# Maiskolben_THT.net
KiCad netlist of a schematic drawn in EAGLE
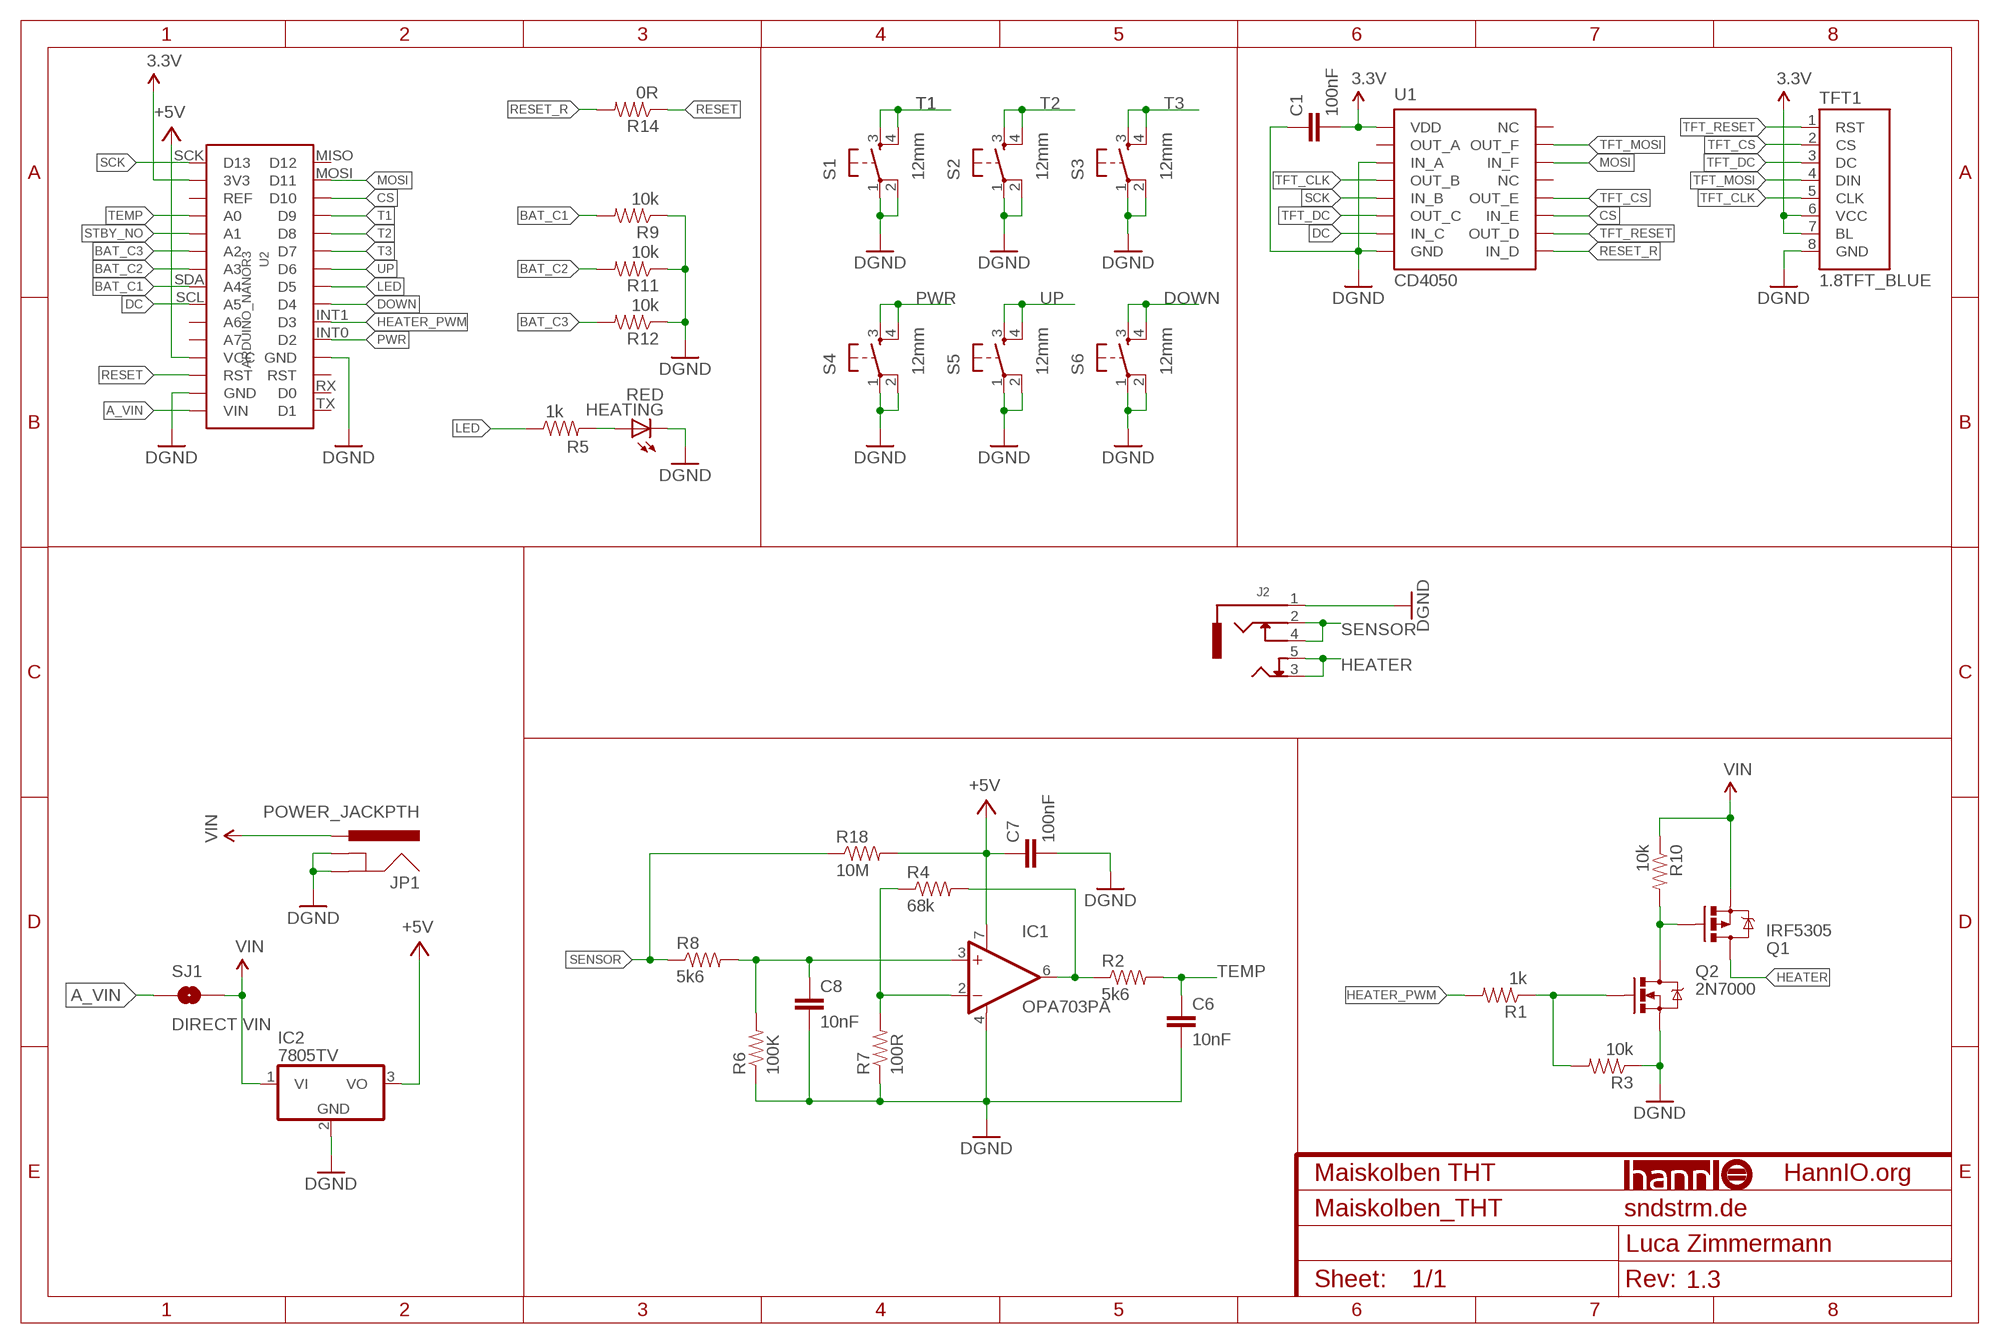
[diagram p0: schematic, sheet 1]

(export (version "E")
  (design (tool "Eeschema 10.0.6"))
  (components
    (comp (ref "C1")
      (value "100nF")
      (footprint "eagle-import:CAP-PTH-SMALLEZ")
      (libsource (lib "eagle-import") (part "CAPEZ"))
    )
    (comp (ref "C6")
      (value "10nF")
      (footprint "eagle-import:CAP-PTH-SMALLEZ")
      (libsource (lib "eagle-import") (part "CAPEZ"))
    )
    (comp (ref "C7")
      (value "100nF")
      (footprint "eagle-import:CAP-PTH-SMALLEZ")
      (libsource (lib "eagle-import") (part "CAPEZ"))
    )
    (comp (ref "C8")
      (value "10nF")
      (footprint "eagle-import:CAP-PTH-SMALLEZ")
      (libsource (lib "eagle-import") (part "CAPEZ"))
    )
    (comp (ref "HEATING")
      (value "RED")
      (footprint "eagle-import:LED5MM")
      (libsource (lib "eagle-import") (part "LED5MM"))
    )
    (comp (ref "IC1")
      (value "OPA703PA")
      (footprint "eagle-import:DIL08")
      (fields (field (name "MPN") "OPA340PA"))
      (libsource (lib "eagle-import") (part "OPA340P"))
    )
    (comp (ref "IC2")
      (value "7805TV")
      (footprint "eagle-import:TO220V")
      (libsource (lib "eagle-import") (part "78TV05"))
    )
    (comp (ref "J2")
      (value "AUDIO_JACK_5PEBS_35")
      (footprint "eagle-import:EBS_35")
      (libsource (lib "eagle-import") (part "AUDIO_JACK_5PEBS_35"))
    )
    (comp (ref "JP1")
      (value "POWER_JACKPTH")
      (footprint "eagle-import:POWER_JACK_PTH")
      (libsource (lib "eagle-import") (part "POWER_JACKPTH"))
    )
    (comp (ref "Q1")
      (value "IRF5305")
      (footprint "eagle-import:TO220V")
      (libsource (lib "eagle-import") (part "MOSFET-PCHANNELFQP27P06"))
    )
    (comp (ref "Q2")
      (value "2N7000")
      (footprint "eagle-import:TO-92")
      (libsource (lib "eagle-import") (part "MOSFET-NCHANNEL2N7000"))
    )
    (comp (ref "R1")
      (value "1k")
      (footprint "eagle-import:AXIAL-0.3")
      (libsource (lib "eagle-import") (part "RESISTORAXIAL-0.3"))
    )
    (comp (ref "R2")
      (value "5k6")
      (footprint "eagle-import:AXIAL-0.3")
      (libsource (lib "eagle-import") (part "RESISTORAXIAL-0.3"))
    )
    (comp (ref "R3")
      (value "10k")
      (footprint "eagle-import:AXIAL-0.3")
      (libsource (lib "eagle-import") (part "RESISTORAXIAL-0.3"))
    )
    (comp (ref "R4")
      (value "68k")
      (footprint "eagle-import:AXIAL-0.3")
      (libsource (lib "eagle-import") (part "RESISTORAXIAL-0.3"))
    )
    (comp (ref "R5")
      (value "1k")
      (footprint "eagle-import:AXIAL-0.3")
      (libsource (lib "eagle-import") (part "RESISTORAXIAL-0.3"))
    )
    (comp (ref "R6")
      (value "100K")
      (footprint "eagle-import:AXIAL-0.3")
      (libsource (lib "eagle-import") (part "RESISTORAXIAL-0.3"))
    )
    (comp (ref "R7")
      (value "100R")
      (footprint "eagle-import:AXIAL-0.3")
      (libsource (lib "eagle-import") (part "RESISTORAXIAL-0.3"))
    )
    (comp (ref "R8")
      (value "5k6")
      (footprint "eagle-import:AXIAL-0.3")
      (libsource (lib "eagle-import") (part "RESISTORAXIAL-0.3"))
    )
    (comp (ref "R9")
      (value "10k")
      (footprint "eagle-import:AXIAL-0.3")
      (libsource (lib "eagle-import") (part "RESISTORAXIAL-0.3"))
    )
    (comp (ref "R10")
      (value "10k")
      (footprint "eagle-import:AXIAL-0.3")
      (libsource (lib "eagle-import") (part "RESISTORAXIAL-0.3"))
    )
    (comp (ref "R11")
      (value "10k")
      (footprint "eagle-import:AXIAL-0.3")
      (libsource (lib "eagle-import") (part "RESISTORAXIAL-0.3"))
    )
    (comp (ref "R12")
      (value "10k")
      (footprint "eagle-import:AXIAL-0.3")
      (libsource (lib "eagle-import") (part "RESISTORAXIAL-0.3"))
    )
    (comp (ref "R14")
      (value "0R")
      (footprint "eagle-import:AXIAL-0.3")
      (libsource (lib "eagle-import") (part "RESISTORAXIAL-0.3"))
    )
    (comp (ref "R18")
      (value "10M")
      (footprint "eagle-import:AXIAL-0.3")
      (libsource (lib "eagle-import") (part "RESISTORAXIAL-0.3"))
    )
    (comp (ref "S1")
      (value "12mm")
      (footprint "eagle-import:TACTILE-PTH")
      (libsource (lib "eagle-import") (part "TAC_SWITCHPTH"))
    )
    (comp (ref "S2")
      (value "12mm")
      (footprint "eagle-import:TACTILE-PTH")
      (libsource (lib "eagle-import") (part "TAC_SWITCHPTH"))
    )
    (comp (ref "S3")
      (value "12mm")
      (footprint "eagle-import:TACTILE-PTH")
      (libsource (lib "eagle-import") (part "TAC_SWITCHPTH"))
    )
    (comp (ref "S4")
      (value "12mm")
      (footprint "eagle-import:TACTILE-PTH")
      (libsource (lib "eagle-import") (part "TAC_SWITCHPTH"))
    )
    (comp (ref "S5")
      (value "12mm")
      (footprint "eagle-import:TACTILE-PTH")
      (libsource (lib "eagle-import") (part "TAC_SWITCHPTH"))
    )
    (comp (ref "S6")
      (value "12mm")
      (footprint "eagle-import:TACTILE-PTH")
      (libsource (lib "eagle-import") (part "TAC_SWITCHPTH"))
    )
    (comp (ref "SJ1")
      (value "DIRECT VIN")
      (footprint "eagle-import:PAD-JUMPER-2-NO_YES_SILK")
      (libsource (lib "eagle-import") (part "JUMPER-PAD-2-NOYES_SILK"))
    )
    (comp (ref "TFT1")
      (value "1.8TFT_BLUE")
      (footprint "eagle-import:1.8TFT_BLUE")
      (libsource (lib "eagle-import") (part "1.8TFT_BLUE"))
    )
    (comp (ref "U$1")
      (value "HANNIO_MEDIUM")
      (footprint "eagle-import:HANNIO_MEDIUM")
      (libsource (lib "eagle-import") (part "HANNIO_MEDIUM"))
    )
    (comp (ref "U1")
      (value "CD4050DIP16")
      (footprint "eagle-import:CD4050")
      (libsource (lib "eagle-import") (part "CD4050DIP16"))
    )
    (comp (ref "U2")
      (value "ARDUINO_NANOR3")
      (footprint "eagle-import:ARDUINO-NANO")
      (libsource (lib "eagle-import") (part "ARDUINO_NANOR3"))
    )
  )
  (nets
    (net (code "1") (name "+5V") (class "Default")
      (node (ref "C7") (pin "1") (pinfunction "1_1") (pintype "passive"))
      (node (ref "IC1") (pin "7") (pinfunction "V+_7") (pintype "power_in"))
      (node (ref "IC2") (pin "3") (pinfunction "VO_3") (pintype "passive"))
      (node (ref "R18") (pin "P$2") (pinfunction "2_P$2") (pintype "passive"))
      (node (ref "U2") (pin "VCC") (pinfunction "VCC_VCC") (pintype "power_in"))
    )
    (net (code "2") (name "3.3V") (class "Default")
      (node (ref "C1") (pin "2") (pinfunction "2_2") (pintype "passive"))
      (node (ref "TFT1") (pin "6") (pinfunction "VCC_6") (pintype "power_in"))
      (node (ref "TFT1") (pin "7") (pinfunction "BL_7") (pintype "passive"))
      (node (ref "U1") (pin "VDD") (pinfunction "VDD_VDD") (pintype "power_in"))
      (node (ref "U2") (pin "3V3") (pinfunction "3V3_3V3") (pintype "power_in"))
    )
    (net (code "3") (name "A_VIN") (class "Default")
      (node (ref "SJ1") (pin "1") (pinfunction "1_1") (pintype "passive"))
      (node (ref "U2") (pin "VIN") (pinfunction "VIN_VIN") (pintype "power_in"))
    )
    (net (code "4") (name "BAT_C1") (class "Default")
      (node (ref "R9") (pin "P$2") (pinfunction "2_P$2") (pintype "passive"))
      (node (ref "U2") (pin "SDA") (pinfunction "A4_SDA") (pintype "bidirectional"))
    )
    (net (code "5") (name "BAT_C2") (class "Default")
      (node (ref "R11") (pin "P$2") (pinfunction "2_P$2") (pintype "passive"))
      (node (ref "U2") (pin "A3") (pinfunction "A3_A3") (pintype "bidirectional"))
    )
    (net (code "6") (name "BAT_C3") (class "Default")
      (node (ref "R12") (pin "P$2") (pinfunction "2_P$2") (pintype "passive"))
      (node (ref "U2") (pin "A2") (pinfunction "A2_A2") (pintype "bidirectional"))
    )
    (net (code "7") (name "CS") (class "Default")
      (node (ref "U1") (pin "IN_E") (pinfunction "IN_E_IN_E") (pintype "bidirectional"))
      (node (ref "U2") (pin "D10") (pinfunction "D10_D10") (pintype "bidirectional"))
    )
    (net (code "8") (name "DC") (class "Default")
      (node (ref "U1") (pin "IN_C") (pinfunction "IN_C_IN_C") (pintype "bidirectional"))
      (node (ref "U2") (pin "SCL") (pinfunction "A5_SCL") (pintype "bidirectional"))
    )
    (net (code "9") (name "DGND") (class "Default")
      (node (ref "C1") (pin "1") (pinfunction "1_1") (pintype "passive"))
      (node (ref "C6") (pin "2") (pinfunction "2_2") (pintype "passive"))
      (node (ref "C7") (pin "2") (pinfunction "2_2") (pintype "passive"))
      (node (ref "C8") (pin "2") (pinfunction "2_2") (pintype "passive"))
      (node (ref "HEATING") (pin "K") (pinfunction "C_K") (pintype "passive"))
      (node (ref "IC1") (pin "4") (pinfunction "V-_4") (pintype "power_in"))
      (node (ref "IC2") (pin "2") (pinfunction "GND_2") (pintype "passive"))
      (node (ref "J2") (pin "1") (pinfunction "GND_1") (pintype "bidirectional"))
      (node (ref "JP1") (pin "GND") (pinfunction "GND_GND") (pintype "bidirectional"))
      (node (ref "JP1") (pin "GNDBREAK") (pinfunction "GNDBREAK_GNDBREAK") (pintype "bidirectional"))
      (node (ref "Q2") (pin "1") (pinfunction "S_1") (pintype "passive"))
      (node (ref "R11") (pin "P$1") (pinfunction "1_P$1") (pintype "passive"))
      (node (ref "R12") (pin "P$1") (pinfunction "1_P$1") (pintype "passive"))
      (node (ref "R3") (pin "P$1") (pinfunction "1_P$1") (pintype "passive"))
      (node (ref "R6") (pin "P$1") (pinfunction "1_P$1") (pintype "passive"))
      (node (ref "R7") (pin "P$1") (pinfunction "1_P$1") (pintype "passive"))
      (node (ref "R9") (pin "P$1") (pinfunction "1_P$1") (pintype "passive"))
      (node (ref "S1") (pin "1") (pinfunction "1_1") (pintype "passive"))
      (node (ref "S1") (pin "2") (pinfunction "2_2") (pintype "passive"))
      (node (ref "S2") (pin "1") (pinfunction "1_1") (pintype "passive"))
      (node (ref "S2") (pin "2") (pinfunction "2_2") (pintype "passive"))
      (node (ref "S3") (pin "1") (pinfunction "1_1") (pintype "passive"))
      (node (ref "S3") (pin "2") (pinfunction "2_2") (pintype "passive"))
      (node (ref "S4") (pin "1") (pinfunction "1_1") (pintype "passive"))
      (node (ref "S4") (pin "2") (pinfunction "2_2") (pintype "passive"))
      (node (ref "S5") (pin "1") (pinfunction "1_1") (pintype "passive"))
      (node (ref "S5") (pin "2") (pinfunction "2_2") (pintype "passive"))
      (node (ref "S6") (pin "1") (pinfunction "1_1") (pintype "passive"))
      (node (ref "S6") (pin "2") (pinfunction "2_2") (pintype "passive"))
      (node (ref "TFT1") (pin "8") (pinfunction "GND_8") (pintype "power_in"))
      (node (ref "U1") (pin "GND") (pinfunction "GND_GND") (pintype "power_in"))
      (node (ref "U1") (pin "IN_A") (pinfunction "IN_A_IN_A") (pintype "bidirectional"))
      (node (ref "U2") (pin "GND@1") (pinfunction "GND_GND@1") (pintype "power_in"))
      (node (ref "U2") (pin "GND@2") (pinfunction "GND_GND@2") (pintype "power_in"))
    )
    (net (code "10") (name "DOWN") (class "Default")
      (node (ref "S6") (pin "3") (pinfunction "3_3") (pintype "passive"))
      (node (ref "S6") (pin "4") (pinfunction "4_4") (pintype "passive"))
      (node (ref "U2") (pin "D4") (pinfunction "D4_D4") (pintype "bidirectional"))
    )
    (net (code "11") (name "HEATER") (class "Default")
      (node (ref "J2") (pin "3") (pinfunction "TIP_3") (pintype "bidirectional"))
      (node (ref "J2") (pin "5") (pinfunction "TIP_NC_5") (pintype "bidirectional"))
      (node (ref "Q1") (pin "2") (pinfunction "D_2") (pintype "passive"))
    )
    (net (code "12") (name "HEATER_PWM") (class "Default")
      (node (ref "R1") (pin "P$2") (pinfunction "2_P$2") (pintype "passive"))
      (node (ref "U2") (pin "INT1") (pinfunction "D3_INT1") (pintype "bidirectional"))
    )
    (net (code "13") (name "LED") (class "Default")
      (node (ref "R5") (pin "P$1") (pinfunction "1_P$1") (pintype "passive"))
      (node (ref "U2") (pin "D5") (pinfunction "D5_D5") (pintype "bidirectional"))
    )
    (net (code "14") (name "MOSI") (class "Default")
      (node (ref "U1") (pin "IN_F") (pinfunction "IN_F_IN_F") (pintype "bidirectional"))
      (node (ref "U2") (pin "MOSI") (pinfunction "D11_MOSI") (pintype "bidirectional"))
    )
    (net (code "15") (name "Net-(IC1-+IN)") (class "Default")
      (node (ref "C8") (pin "1") (pinfunction "1_1") (pintype "passive"))
      (node (ref "IC1") (pin "3") (pinfunction "+IN_3") (pintype "input"))
      (node (ref "R6") (pin "P$2") (pinfunction "2_P$2") (pintype "passive"))
      (node (ref "R8") (pin "P$2") (pinfunction "2_P$2") (pintype "passive"))
    )
    (net (code "16") (name "Net-(IC1--IN)") (class "Default")
      (node (ref "IC1") (pin "2") (pinfunction "-IN_2") (pintype "input"))
      (node (ref "R4") (pin "P$1") (pinfunction "1_P$1") (pintype "passive"))
      (node (ref "R7") (pin "P$2") (pinfunction "2_P$2") (pintype "passive"))
    )
    (net (code "17") (name "Net-(IC1-OUT)") (class "Default")
      (node (ref "IC1") (pin "6") (pinfunction "OUT_6") (pintype "output"))
      (node (ref "R2") (pin "P$1") (pinfunction "1_P$1") (pintype "passive"))
      (node (ref "R4") (pin "P$2") (pinfunction "2_P$2") (pintype "passive"))
    )
    (net (code "18") (name "Net-(Q1-G)") (class "Default")
      (node (ref "Q1") (pin "1") (pinfunction "G_1") (pintype "passive"))
      (node (ref "Q2") (pin "3") (pinfunction "D_3") (pintype "passive"))
      (node (ref "R10") (pin "P$2") (pinfunction "2_P$2") (pintype "passive"))
    )
    (net (code "19") (name "Net-(Q2-G)") (class "Default")
      (node (ref "Q2") (pin "2") (pinfunction "G_2") (pintype "passive"))
      (node (ref "R1") (pin "P$1") (pinfunction "1_P$1") (pintype "passive"))
      (node (ref "R3") (pin "P$2") (pinfunction "2_P$2") (pintype "passive"))
    )
    (net (code "20") (name "Net-(R5-2)") (class "Default")
      (node (ref "HEATING") (pin "A") (pinfunction "A_A") (pintype "passive"))
      (node (ref "R5") (pin "P$2") (pinfunction "2_P$2") (pintype "passive"))
    )
    (net (code "21") (name "PWR") (class "Default")
      (node (ref "S4") (pin "3") (pinfunction "3_3") (pintype "passive"))
      (node (ref "S4") (pin "4") (pinfunction "4_4") (pintype "passive"))
      (node (ref "U2") (pin "INT0") (pinfunction "D2_INT0") (pintype "bidirectional"))
    )
    (net (code "22") (name "RESET") (class "Default")
      (node (ref "R14") (pin "P$1") (pinfunction "1_P$1") (pintype "passive"))
      (node (ref "U2") (pin "RST@2") (pinfunction "RST_RST@2") (pintype "bidirectional"))
    )
    (net (code "23") (name "RESET_R") (class "Default")
      (node (ref "R14") (pin "P$2") (pinfunction "2_P$2") (pintype "passive"))
      (node (ref "U1") (pin "IN_D") (pinfunction "IN_D_IN_D") (pintype "bidirectional"))
    )
    (net (code "24") (name "SCK") (class "Default")
      (node (ref "U1") (pin "IN_B") (pinfunction "IN_B_IN_B") (pintype "bidirectional"))
      (node (ref "U2") (pin "SCK") (pinfunction "D13_SCK") (pintype "bidirectional"))
    )
    (net (code "25") (name "SENSOR") (class "Default")
      (node (ref "J2") (pin "2") (pinfunction "RING_2") (pintype "bidirectional"))
      (node (ref "J2") (pin "4") (pinfunction "RING_NC_4") (pintype "bidirectional"))
      (node (ref "R18") (pin "P$1") (pinfunction "1_P$1") (pintype "passive"))
      (node (ref "R8") (pin "P$1") (pinfunction "1_P$1") (pintype "passive"))
    )
    (net (code "26") (name "STBY_NO") (class "Default")
      (node (ref "U2") (pin "A1") (pinfunction "A1_A1") (pintype "bidirectional"))
    )
    (net (code "27") (name "T1") (class "Default")
      (node (ref "S1") (pin "3") (pinfunction "3_3") (pintype "passive"))
      (node (ref "S1") (pin "4") (pinfunction "4_4") (pintype "passive"))
      (node (ref "U2") (pin "D9") (pinfunction "D9_D9") (pintype "bidirectional"))
    )
    (net (code "28") (name "T2") (class "Default")
      (node (ref "S2") (pin "3") (pinfunction "3_3") (pintype "passive"))
      (node (ref "S2") (pin "4") (pinfunction "4_4") (pintype "passive"))
      (node (ref "U2") (pin "D8") (pinfunction "D8_D8") (pintype "bidirectional"))
    )
    (net (code "29") (name "T3") (class "Default")
      (node (ref "S3") (pin "3") (pinfunction "3_3") (pintype "passive"))
      (node (ref "S3") (pin "4") (pinfunction "4_4") (pintype "passive"))
      (node (ref "U2") (pin "D7") (pinfunction "D7_D7") (pintype "bidirectional"))
    )
    (net (code "30") (name "TEMP") (class "Default")
      (node (ref "C6") (pin "1") (pinfunction "1_1") (pintype "passive"))
      (node (ref "R2") (pin "P$2") (pinfunction "2_P$2") (pintype "passive"))
      (node (ref "U2") (pin "A0") (pinfunction "A0_A0") (pintype "bidirectional"))
    )
    (net (code "31") (name "TFT_CLK") (class "Default")
      (node (ref "TFT1") (pin "5") (pinfunction "CLK_5") (pintype "input"))
      (node (ref "U1") (pin "OUT_B") (pinfunction "OUT_B_OUT_B") (pintype "bidirectional"))
    )
    (net (code "32") (name "TFT_CS") (class "Default")
      (node (ref "TFT1") (pin "2") (pinfunction "CS_2") (pintype "input"))
      (node (ref "U1") (pin "OUT_E") (pinfunction "OUT_E_OUT_E") (pintype "bidirectional"))
    )
    (net (code "33") (name "TFT_DC") (class "Default")
      (node (ref "TFT1") (pin "3") (pinfunction "DC_3") (pintype "input"))
      (node (ref "U1") (pin "OUT_C") (pinfunction "OUT_C_OUT_C") (pintype "bidirectional"))
    )
    (net (code "34") (name "TFT_MOSI") (class "Default")
      (node (ref "TFT1") (pin "4") (pinfunction "DIN_4") (pintype "input"))
      (node (ref "U1") (pin "OUT_F") (pinfunction "OUT_F_OUT_F") (pintype "bidirectional"))
    )
    (net (code "35") (name "TFT_RESET") (class "Default")
      (node (ref "TFT1") (pin "1") (pinfunction "RST_1") (pintype "input"))
      (node (ref "U1") (pin "OUT_D") (pinfunction "OUT_D_OUT_D") (pintype "bidirectional"))
    )
    (net (code "36") (name "UP") (class "Default")
      (node (ref "S5") (pin "3") (pinfunction "3_3") (pintype "passive"))
      (node (ref "S5") (pin "4") (pinfunction "4_4") (pintype "passive"))
      (node (ref "U2") (pin "D6") (pinfunction "D6_D6") (pintype "bidirectional"))
    )
    (net (code "37") (name "VIN") (class "Default")
      (node (ref "IC2") (pin "1") (pinfunction "VI_1") (pintype "input"))
      (node (ref "JP1") (pin "PWR") (pinfunction "PWR_PWR") (pintype "bidirectional"))
      (node (ref "Q1") (pin "3") (pinfunction "S_3") (pintype "passive"))
      (node (ref "R10") (pin "P$1") (pinfunction "1_P$1") (pintype "passive"))
      (node (ref "SJ1") (pin "2") (pinfunction "2_2") (pintype "passive"))
    )
    (net (code "38") (name "unconnected-(U1-NC-PadNC@1)") (class "Default")
      (node (ref "U1") (pin "NC@1") (pinfunction "NC_NC@1") (pintype "no_connect"))
    )
    (net (code "39") (name "unconnected-(U1-NC-PadNC@2)") (class "Default")
      (node (ref "U1") (pin "NC@2") (pinfunction "NC_NC@2") (pintype "no_connect"))
    )
    (net (code "40") (name "unconnected-(U1-PadOUT_A)") (class "Default")
      (node (ref "U1") (pin "OUT_A") (pinfunction "OUT_A_OUT_A") (pintype "bidirectional"))
    )
    (net (code "41") (name "unconnected-(U2-D0-PadRX)") (class "Default")
      (node (ref "U2") (pin "RX") (pinfunction "D0_RX") (pintype "bidirectional"))
    )
    (net (code "42") (name "unconnected-(U2-D1-PadTX)") (class "Default")
      (node (ref "U2") (pin "TX") (pinfunction "D1_TX") (pintype "bidirectional"))
    )
    (net (code "43") (name "unconnected-(U2-D12-PadMISO)") (class "Default")
      (node (ref "U2") (pin "MISO") (pinfunction "D12_MISO") (pintype "bidirectional"))
    )
    (net (code "44") (name "unconnected-(U2-PadA6)") (class "Default")
      (node (ref "U2") (pin "A6") (pinfunction "A6_A6") (pintype "bidirectional"))
    )
    (net (code "45") (name "unconnected-(U2-PadA7)") (class "Default")
      (node (ref "U2") (pin "A7") (pinfunction "A7_A7") (pintype "bidirectional"))
    )
    (net (code "46") (name "unconnected-(U2-PadREF)") (class "Default")
      (node (ref "U2") (pin "REF") (pinfunction "REF_REF") (pintype "bidirectional"))
    )
    (net (code "47") (name "unconnected-(U2-RST-PadRST@1)") (class "Default")
      (node (ref "U2") (pin "RST@1") (pinfunction "RST_RST@1") (pintype "bidirectional"))
    )
  )
)
